# Arena2_0.net
KiCad netlist of a schematic drawn in Altium Designer
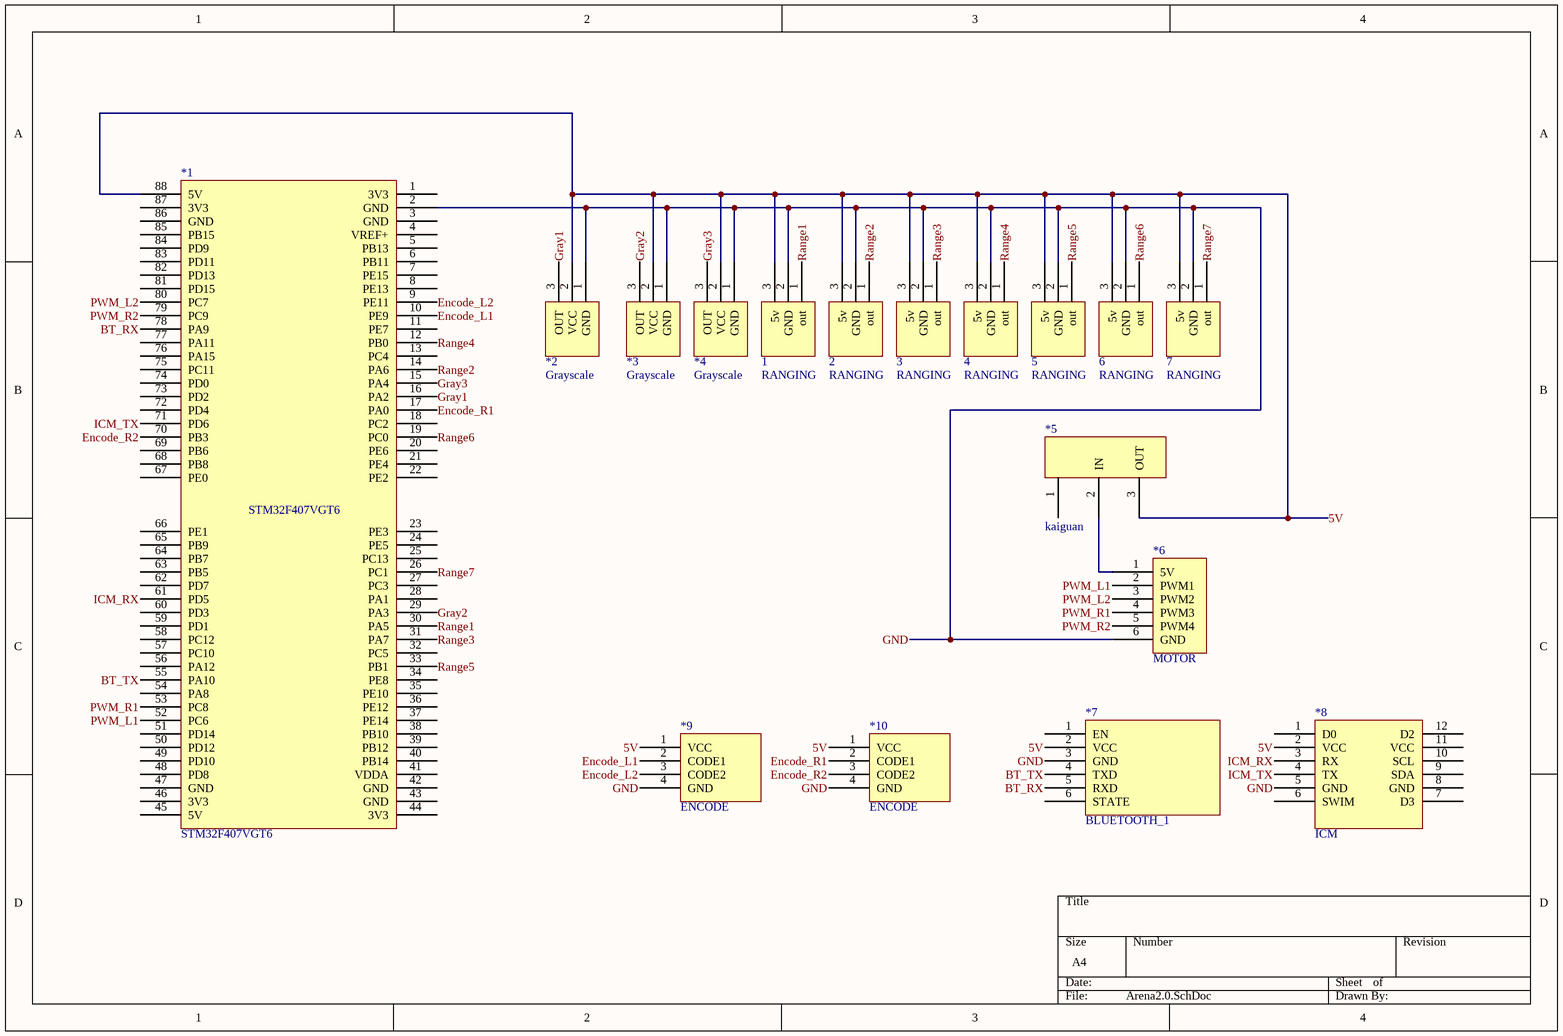
[diagram p0: Arena2.0.SchDoc]

(export (version "E")
  (design (tool "Eeschema 10.0.6"))
  (components
    (comp (ref "*1")
      (value "STM32F407VGT6")
      (footprint "STM32F407VGT6")
      (libsource (lib "Arena") (part "STM32F407VGT6"))
    )
    (comp (ref "*2")
      (value "Grayscale")
      (footprint "PH2.0-L-Z-3P")
      (libsource (lib "Arena") (part "Grayscale"))
    )
    (comp (ref "*3")
      (value "Grayscale")
      (footprint "PH2.0-L-Z-3P")
      (libsource (lib "Arena") (part "Grayscale"))
    )
    (comp (ref "*4")
      (value "Grayscale")
      (footprint "PH2.0-L-Z-3P")
      (libsource (lib "Arena") (part "Grayscale"))
    )
    (comp (ref "*5") (value "kaiguan") (footprint "kaiguan") (libsource (lib "Arena") (part "kaiguan")))
    (comp (ref "*6") (value "MOTOR") (footprint "PH2.0-L-Z-6P") (libsource (lib "Arena") (part "MOTOR")))
    (comp (ref "*7")
      (value "BLUETOOTH_1")
      (footprint "bluetooth")
      (libsource (lib "Arena") (part "BLUETOOTH_1"))
    )
    (comp (ref "*8") (value "ICM") (footprint "ICM") (libsource (lib "Arena") (part "ICM")))
    (comp (ref "*9") (value "ENCODE") (footprint "PH2.0-L-Z-4P") (libsource (lib "Arena") (part "ENCODE")))
    (comp (ref "*10") (value "ENCODE") (footprint "PH2.0-L-Z-4P") (libsource (lib "Arena") (part "ENCODE")))
    (comp (ref "1") (value "RANGING") (footprint "PH2.0-L-Z-3P") (libsource (lib "Arena") (part "RANGING")))
    (comp (ref "2") (value "RANGING") (footprint "PH2.0-L-Z-3P") (libsource (lib "Arena") (part "RANGING")))
    (comp (ref "3") (value "RANGING") (footprint "PH2.0-L-Z-3P") (libsource (lib "Arena") (part "RANGING")))
    (comp (ref "4") (value "RANGING") (footprint "PH2.0-L-Z-3P") (libsource (lib "Arena") (part "RANGING")))
    (comp (ref "5") (value "RANGING") (footprint "PH2.0-L-Z-3P") (libsource (lib "Arena") (part "RANGING")))
    (comp (ref "6") (value "RANGING") (footprint "PH2.0-L-Z-3P") (libsource (lib "Arena") (part "RANGING")))
    (comp (ref "7") (value "RANGING") (footprint "PH2.0-L-Z-3P") (libsource (lib "Arena") (part "RANGING")))
  )
  (nets
    (net (code "1") (name "/5V") (class "Default")
      (node (ref "*1") (pin "88") (pinfunction "5V_88") (pintype "passive"))
      (node (ref "*10") (pin "1") (pinfunction "VCC_1") (pintype "passive"))
      (node (ref "*2") (pin "2") (pinfunction "VCC_2") (pintype "passive"))
      (node (ref "*3") (pin "2") (pinfunction "VCC_2") (pintype "passive"))
      (node (ref "*4") (pin "2") (pinfunction "VCC_2") (pintype "passive"))
      (node (ref "*5") (pin "3") (pinfunction "OUT_3") (pintype "passive"))
      (node (ref "*7") (pin "2") (pinfunction "VCC_2") (pintype "passive"))
      (node (ref "*8") (pin "2") (pinfunction "VCC_2") (pintype "passive"))
      (node (ref "*9") (pin "1") (pinfunction "VCC_1") (pintype "passive"))
      (node (ref "1") (pin "3") (pinfunction "5v_3") (pintype "passive"))
      (node (ref "2") (pin "3") (pinfunction "5v_3") (pintype "passive"))
      (node (ref "3") (pin "3") (pinfunction "5v_3") (pintype "passive"))
      (node (ref "4") (pin "3") (pinfunction "5v_3") (pintype "passive"))
      (node (ref "5") (pin "3") (pinfunction "5v_3") (pintype "passive"))
      (node (ref "6") (pin "3") (pinfunction "5v_3") (pintype "passive"))
      (node (ref "7") (pin "3") (pinfunction "5v_3") (pintype "passive"))
    )
    (net (code "2") (name "/BT_RX") (class "Default")
      (node (ref "*1") (pin "78") (pinfunction "PA9_78") (pintype "passive"))
      (node (ref "*7") (pin "5") (pinfunction "RXD_5") (pintype "passive"))
    )
    (net (code "3") (name "/BT_TX") (class "Default")
      (node (ref "*1") (pin "55") (pinfunction "PA10_55") (pintype "passive"))
      (node (ref "*7") (pin "4") (pinfunction "TXD_4") (pintype "passive"))
    )
    (net (code "4") (name "/Encode_L1") (class "Default")
      (node (ref "*1") (pin "10") (pinfunction "PE9_10") (pintype "passive"))
      (node (ref "*9") (pin "2") (pinfunction "CODE1_2") (pintype "passive"))
    )
    (net (code "5") (name "/Encode_L2") (class "Default")
      (node (ref "*1") (pin "9") (pinfunction "PE11_9") (pintype "passive"))
      (node (ref "*9") (pin "3") (pinfunction "CODE2_3") (pintype "passive"))
    )
    (net (code "6") (name "/Encode_R1") (class "Default")
      (node (ref "*1") (pin "17") (pinfunction "PA0_17") (pintype "passive"))
      (node (ref "*10") (pin "2") (pinfunction "CODE1_2") (pintype "passive"))
    )
    (net (code "7") (name "/Encode_R2") (class "Default")
      (node (ref "*1") (pin "70") (pinfunction "PB3_70") (pintype "passive"))
      (node (ref "*10") (pin "3") (pinfunction "CODE2_3") (pintype "passive"))
    )
    (net (code "8") (name "/GND") (class "Default")
      (node (ref "*1") (pin "2") (pinfunction "GND_2") (pintype "passive"))
      (node (ref "*10") (pin "4") (pinfunction "GND_4") (pintype "passive"))
      (node (ref "*2") (pin "1") (pinfunction "GND_1") (pintype "passive"))
      (node (ref "*3") (pin "1") (pinfunction "GND_1") (pintype "passive"))
      (node (ref "*4") (pin "1") (pinfunction "GND_1") (pintype "passive"))
      (node (ref "*6") (pin "6") (pinfunction "GND_6") (pintype "passive"))
      (node (ref "*7") (pin "3") (pinfunction "GND_3") (pintype "passive"))
      (node (ref "*8") (pin "5") (pinfunction "GND_5") (pintype "passive"))
      (node (ref "*9") (pin "4") (pinfunction "GND_4") (pintype "passive"))
      (node (ref "1") (pin "2") (pinfunction "GND_2") (pintype "passive"))
      (node (ref "2") (pin "2") (pinfunction "GND_2") (pintype "passive"))
      (node (ref "3") (pin "2") (pinfunction "GND_2") (pintype "passive"))
      (node (ref "4") (pin "2") (pinfunction "GND_2") (pintype "passive"))
      (node (ref "5") (pin "2") (pinfunction "GND_2") (pintype "passive"))
      (node (ref "6") (pin "2") (pinfunction "GND_2") (pintype "passive"))
      (node (ref "7") (pin "2") (pinfunction "GND_2") (pintype "passive"))
    )
    (net (code "9") (name "/Gray1") (class "Default")
      (node (ref "*1") (pin "16") (pinfunction "PA2_16") (pintype "passive"))
      (node (ref "*2") (pin "3") (pinfunction "OUT_3") (pintype "passive"))
    )
    (net (code "10") (name "/Gray2") (class "Default")
      (node (ref "*1") (pin "29") (pinfunction "PA3_29") (pintype "passive"))
      (node (ref "*3") (pin "3") (pinfunction "OUT_3") (pintype "passive"))
    )
    (net (code "11") (name "/Gray3") (class "Default")
      (node (ref "*1") (pin "15") (pinfunction "PA4_15") (pintype "passive"))
      (node (ref "*4") (pin "3") (pinfunction "OUT_3") (pintype "passive"))
    )
    (net (code "12") (name "/ICM_RX") (class "Default")
      (node (ref "*1") (pin "61") (pinfunction "PD5_61") (pintype "passive"))
      (node (ref "*8") (pin "3") (pinfunction "RX_3") (pintype "passive"))
    )
    (net (code "13") (name "/ICM_TX") (class "Default")
      (node (ref "*1") (pin "71") (pinfunction "PD6_71") (pintype "passive"))
      (node (ref "*8") (pin "4") (pinfunction "TX_4") (pintype "passive"))
    )
    (net (code "14") (name "/PWM_L1") (class "Default")
      (node (ref "*1") (pin "52") (pinfunction "PC6_52") (pintype "passive"))
      (node (ref "*6") (pin "2") (pinfunction "PWM1_2") (pintype "passive"))
    )
    (net (code "15") (name "/PWM_L2") (class "Default")
      (node (ref "*1") (pin "80") (pinfunction "PC7_80") (pintype "passive"))
      (node (ref "*6") (pin "3") (pinfunction "PWM2_3") (pintype "passive"))
    )
    (net (code "16") (name "/PWM_R1") (class "Default")
      (node (ref "*1") (pin "53") (pinfunction "PC8_53") (pintype "passive"))
      (node (ref "*6") (pin "4") (pinfunction "PWM3_4") (pintype "passive"))
    )
    (net (code "17") (name "/PWM_R2") (class "Default")
      (node (ref "*1") (pin "79") (pinfunction "PC9_79") (pintype "passive"))
      (node (ref "*6") (pin "5") (pinfunction "PWM4_5") (pintype "passive"))
    )
    (net (code "18") (name "/Range1") (class "Default")
      (node (ref "*1") (pin "30") (pinfunction "PA5_30") (pintype "passive"))
      (node (ref "1") (pin "1") (pinfunction "out_1") (pintype "passive"))
    )
    (net (code "19") (name "/Range2") (class "Default")
      (node (ref "*1") (pin "14") (pinfunction "PA6_14") (pintype "passive"))
      (node (ref "2") (pin "1") (pinfunction "out_1") (pintype "passive"))
    )
    (net (code "20") (name "/Range3") (class "Default")
      (node (ref "*1") (pin "31") (pinfunction "PA7_31") (pintype "passive"))
      (node (ref "3") (pin "1") (pinfunction "out_1") (pintype "passive"))
    )
    (net (code "21") (name "/Range4") (class "Default")
      (node (ref "*1") (pin "12") (pinfunction "PB0_12") (pintype "passive"))
      (node (ref "4") (pin "1") (pinfunction "out_1") (pintype "passive"))
    )
    (net (code "22") (name "/Range5") (class "Default")
      (node (ref "*1") (pin "33") (pinfunction "PB1_33") (pintype "passive"))
      (node (ref "5") (pin "1") (pinfunction "out_1") (pintype "passive"))
    )
    (net (code "23") (name "/Range6") (class "Default")
      (node (ref "*1") (pin "19") (pinfunction "PC0_19") (pintype "passive"))
      (node (ref "6") (pin "1") (pinfunction "out_1") (pintype "passive"))
    )
    (net (code "24") (name "/Range7") (class "Default")
      (node (ref "*1") (pin "26") (pinfunction "PC1_26") (pintype "passive"))
      (node (ref "7") (pin "1") (pinfunction "out_1") (pintype "passive"))
    )
    (net (code "25") (name "Net-(*5-IN)") (class "Default")
      (node (ref "*5") (pin "2") (pinfunction "IN_2") (pintype "passive"))
      (node (ref "*6") (pin "1") (pinfunction "5V_1") (pintype "passive"))
    )
    (net (code "26") (name "unconnected-(*1-3V3-Pad1)") (class "Default")
      (node (ref "*1") (pin "1") (pinfunction "3V3_1") (pintype "passive"))
    )
    (net (code "27") (name "unconnected-(*1-3V3-Pad44)") (class "Default")
      (node (ref "*1") (pin "44") (pinfunction "3V3_44") (pintype "passive"))
    )
    (net (code "28") (name "unconnected-(*1-3V3-Pad46)") (class "Default")
      (node (ref "*1") (pin "46") (pinfunction "3V3_46") (pintype "passive"))
    )
    (net (code "29") (name "unconnected-(*1-3V3-Pad87)") (class "Default")
      (node (ref "*1") (pin "87") (pinfunction "3V3_87") (pintype "passive"))
    )
    (net (code "30") (name "unconnected-(*1-5V-Pad45)") (class "Default")
      (node (ref "*1") (pin "45") (pinfunction "5V_45") (pintype "passive"))
    )
    (net (code "31") (name "unconnected-(*1-GND-Pad3)") (class "Default")
      (node (ref "*1") (pin "3") (pinfunction "GND_3") (pintype "passive"))
    )
    (net (code "32") (name "unconnected-(*1-GND-Pad42)") (class "Default")
      (node (ref "*1") (pin "42") (pinfunction "GND_42") (pintype "passive"))
    )
    (net (code "33") (name "unconnected-(*1-GND-Pad43)") (class "Default")
      (node (ref "*1") (pin "43") (pinfunction "GND_43") (pintype "passive"))
    )
    (net (code "34") (name "unconnected-(*1-GND-Pad47)") (class "Default")
      (node (ref "*1") (pin "47") (pinfunction "GND_47") (pintype "passive"))
    )
    (net (code "35") (name "unconnected-(*1-GND-Pad86)") (class "Default")
      (node (ref "*1") (pin "86") (pinfunction "GND_86") (pintype "passive"))
    )
    (net (code "36") (name "unconnected-(*1-PA1-Pad28)") (class "Default")
      (node (ref "*1") (pin "28") (pinfunction "PA1_28") (pintype "passive"))
    )
    (net (code "37") (name "unconnected-(*1-PA8-Pad54)") (class "Default")
      (node (ref "*1") (pin "54") (pinfunction "PA8_54") (pintype "passive"))
    )
    (net (code "38") (name "unconnected-(*1-PA11-Pad77)") (class "Default")
      (node (ref "*1") (pin "77") (pinfunction "PA11_77") (pintype "passive"))
    )
    (net (code "39") (name "unconnected-(*1-PA12-Pad56)") (class "Default")
      (node (ref "*1") (pin "56") (pinfunction "PA12_56") (pintype "passive"))
    )
    (net (code "40") (name "unconnected-(*1-PA15-Pad76)") (class "Default")
      (node (ref "*1") (pin "76") (pinfunction "PA15_76") (pintype "passive"))
    )
    (net (code "41") (name "unconnected-(*1-PB5-Pad63)") (class "Default")
      (node (ref "*1") (pin "63") (pinfunction "PB5_63") (pintype "passive"))
    )
    (net (code "42") (name "unconnected-(*1-PB6-Pad69)") (class "Default")
      (node (ref "*1") (pin "69") (pinfunction "PB6_69") (pintype "passive"))
    )
    (net (code "43") (name "unconnected-(*1-PB7-Pad64)") (class "Default")
      (node (ref "*1") (pin "64") (pinfunction "PB7_64") (pintype "passive"))
    )
    (net (code "44") (name "unconnected-(*1-PB8-Pad68)") (class "Default")
      (node (ref "*1") (pin "68") (pinfunction "PB8_68") (pintype "passive"))
    )
    (net (code "45") (name "unconnected-(*1-PB9-Pad65)") (class "Default")
      (node (ref "*1") (pin "65") (pinfunction "PB9_65") (pintype "passive"))
    )
    (net (code "46") (name "unconnected-(*1-PB10-Pad38)") (class "Default")
      (node (ref "*1") (pin "38") (pinfunction "PB10_38") (pintype "passive"))
    )
    (net (code "47") (name "unconnected-(*1-PB11-Pad6)") (class "Default")
      (node (ref "*1") (pin "6") (pinfunction "PB11_6") (pintype "passive"))
    )
    (net (code "48") (name "unconnected-(*1-PB12-Pad39)") (class "Default")
      (node (ref "*1") (pin "39") (pinfunction "PB12_39") (pintype "passive"))
    )
    (net (code "49") (name "unconnected-(*1-PB13-Pad5)") (class "Default")
      (node (ref "*1") (pin "5") (pinfunction "PB13_5") (pintype "passive"))
    )
    (net (code "50") (name "unconnected-(*1-PB14-Pad40)") (class "Default")
      (node (ref "*1") (pin "40") (pinfunction "PB14_40") (pintype "passive"))
    )
    (net (code "51") (name "unconnected-(*1-PB15-Pad85)") (class "Default")
      (node (ref "*1") (pin "85") (pinfunction "PB15_85") (pintype "passive"))
    )
    (net (code "52") (name "unconnected-(*1-PC2-Pad18)") (class "Default")
      (node (ref "*1") (pin "18") (pinfunction "PC2_18") (pintype "passive"))
    )
    (net (code "53") (name "unconnected-(*1-PC3-Pad27)") (class "Default")
      (node (ref "*1") (pin "27") (pinfunction "PC3_27") (pintype "passive"))
    )
    (net (code "54") (name "unconnected-(*1-PC4-Pad13)") (class "Default")
      (node (ref "*1") (pin "13") (pinfunction "PC4_13") (pintype "passive"))
    )
    (net (code "55") (name "unconnected-(*1-PC5-Pad32)") (class "Default")
      (node (ref "*1") (pin "32") (pinfunction "PC5_32") (pintype "passive"))
    )
    (net (code "56") (name "unconnected-(*1-PC10-Pad57)") (class "Default")
      (node (ref "*1") (pin "57") (pinfunction "PC10_57") (pintype "passive"))
    )
    (net (code "57") (name "unconnected-(*1-PC11-Pad75)") (class "Default")
      (node (ref "*1") (pin "75") (pinfunction "PC11_75") (pintype "passive"))
    )
    (net (code "58") (name "unconnected-(*1-PC12-Pad58)") (class "Default")
      (node (ref "*1") (pin "58") (pinfunction "PC12_58") (pintype "passive"))
    )
    (net (code "59") (name "unconnected-(*1-PC13-Pad25)") (class "Default")
      (node (ref "*1") (pin "25") (pinfunction "PC13_25") (pintype "passive"))
    )
    (net (code "60") (name "unconnected-(*1-PD0-Pad74)") (class "Default")
      (node (ref "*1") (pin "74") (pinfunction "PD0_74") (pintype "passive"))
    )
    (net (code "61") (name "unconnected-(*1-PD1-Pad59)") (class "Default")
      (node (ref "*1") (pin "59") (pinfunction "PD1_59") (pintype "passive"))
    )
    (net (code "62") (name "unconnected-(*1-PD2-Pad73)") (class "Default")
      (node (ref "*1") (pin "73") (pinfunction "PD2_73") (pintype "passive"))
    )
    (net (code "63") (name "unconnected-(*1-PD3-Pad60)") (class "Default")
      (node (ref "*1") (pin "60") (pinfunction "PD3_60") (pintype "passive"))
    )
    (net (code "64") (name "unconnected-(*1-PD4-Pad72)") (class "Default")
      (node (ref "*1") (pin "72") (pinfunction "PD4_72") (pintype "passive"))
    )
    (net (code "65") (name "unconnected-(*1-PD7-Pad62)") (class "Default")
      (node (ref "*1") (pin "62") (pinfunction "PD7_62") (pintype "passive"))
    )
    (net (code "66") (name "unconnected-(*1-PD8-Pad48)") (class "Default")
      (node (ref "*1") (pin "48") (pinfunction "PD8_48") (pintype "passive"))
    )
    (net (code "67") (name "unconnected-(*1-PD9-Pad84)") (class "Default")
      (node (ref "*1") (pin "84") (pinfunction "PD9_84") (pintype "passive"))
    )
    (net (code "68") (name "unconnected-(*1-PD10-Pad49)") (class "Default")
      (node (ref "*1") (pin "49") (pinfunction "PD10_49") (pintype "passive"))
    )
    (net (code "69") (name "unconnected-(*1-PD11-Pad83)") (class "Default")
      (node (ref "*1") (pin "83") (pinfunction "PD11_83") (pintype "passive"))
    )
    (net (code "70") (name "unconnected-(*1-PD12-Pad50)") (class "Default")
      (node (ref "*1") (pin "50") (pinfunction "PD12_50") (pintype "passive"))
    )
    (net (code "71") (name "unconnected-(*1-PD13-Pad82)") (class "Default")
      (node (ref "*1") (pin "82") (pinfunction "PD13_82") (pintype "passive"))
    )
    (net (code "72") (name "unconnected-(*1-PD14-Pad51)") (class "Default")
      (node (ref "*1") (pin "51") (pinfunction "PD14_51") (pintype "passive"))
    )
    (net (code "73") (name "unconnected-(*1-PD15-Pad81)") (class "Default")
      (node (ref "*1") (pin "81") (pinfunction "PD15_81") (pintype "passive"))
    )
    (net (code "74") (name "unconnected-(*1-PE0-Pad67)") (class "Default")
      (node (ref "*1") (pin "67") (pinfunction "PE0_67") (pintype "passive"))
    )
    (net (code "75") (name "unconnected-(*1-PE1-Pad66)") (class "Default")
      (node (ref "*1") (pin "66") (pinfunction "PE1_66") (pintype "passive"))
    )
    (net (code "76") (name "unconnected-(*1-PE2-Pad22)") (class "Default")
      (node (ref "*1") (pin "22") (pinfunction "PE2_22") (pintype "passive"))
    )
    (net (code "77") (name "unconnected-(*1-PE3-Pad23)") (class "Default")
      (node (ref "*1") (pin "23") (pinfunction "PE3_23") (pintype "passive"))
    )
    (net (code "78") (name "unconnected-(*1-PE4-Pad21)") (class "Default")
      (node (ref "*1") (pin "21") (pinfunction "PE4_21") (pintype "passive"))
    )
    (net (code "79") (name "unconnected-(*1-PE5-Pad24)") (class "Default")
      (node (ref "*1") (pin "24") (pinfunction "PE5_24") (pintype "passive"))
    )
    (net (code "80") (name "unconnected-(*1-PE6-Pad20)") (class "Default")
      (node (ref "*1") (pin "20") (pinfunction "PE6_20") (pintype "passive"))
    )
    (net (code "81") (name "unconnected-(*1-PE7-Pad11)") (class "Default")
      (node (ref "*1") (pin "11") (pinfunction "PE7_11") (pintype "passive"))
    )
    (net (code "82") (name "unconnected-(*1-PE8-Pad34)") (class "Default")
      (node (ref "*1") (pin "34") (pinfunction "PE8_34") (pintype "passive"))
    )
    (net (code "83") (name "unconnected-(*1-PE10-Pad35)") (class "Default")
      (node (ref "*1") (pin "35") (pinfunction "PE10_35") (pintype "passive"))
    )
    (net (code "84") (name "unconnected-(*1-PE12-Pad36)") (class "Default")
      (node (ref "*1") (pin "36") (pinfunction "PE12_36") (pintype "passive"))
    )
    (net (code "85") (name "unconnected-(*1-PE13-Pad8)") (class "Default")
      (node (ref "*1") (pin "8") (pinfunction "PE13_8") (pintype "passive"))
    )
    (net (code "86") (name "unconnected-(*1-PE14-Pad37)") (class "Default")
      (node (ref "*1") (pin "37") (pinfunction "PE14_37") (pintype "passive"))
    )
    (net (code "87") (name "unconnected-(*1-PE15-Pad7)") (class "Default")
      (node (ref "*1") (pin "7") (pinfunction "PE15_7") (pintype "passive"))
    )
    (net (code "88") (name "unconnected-(*1-VDDA-Pad41)") (class "Default")
      (node (ref "*1") (pin "41") (pinfunction "VDDA_41") (pintype "passive"))
    )
    (net (code "89") (name "unconnected-(*1-VREF+-Pad4)") (class "Default")
      (node (ref "*1") (pin "4") (pinfunction "VREF+_4") (pintype "passive"))
    )
    (net (code "90") (name "unconnected-(*5-Pad1)") (class "Default")
      (node (ref "*5") (pin "1") (pintype "passive"))
    )
    (net (code "91") (name "unconnected-(*7-EN-Pad1)") (class "Default")
      (node (ref "*7") (pin "1") (pinfunction "EN_1") (pintype "passive"))
    )
    (net (code "92") (name "unconnected-(*7-STATE-Pad6)") (class "Default")
      (node (ref "*7") (pin "6") (pinfunction "STATE_6") (pintype "passive"))
    )
    (net (code "93") (name "unconnected-(*8-D0-Pad1)") (class "Default")
      (node (ref "*8") (pin "1") (pinfunction "D0_1") (pintype "passive"))
    )
    (net (code "94") (name "unconnected-(*8-D2-Pad12)") (class "Default")
      (node (ref "*8") (pin "12") (pinfunction "D2_12") (pintype "passive"))
    )
    (net (code "95") (name "unconnected-(*8-D3-Pad7)") (class "Default")
      (node (ref "*8") (pin "7") (pinfunction "D3_7") (pintype "passive"))
    )
    (net (code "96") (name "unconnected-(*8-GND-Pad8)") (class "Default")
      (node (ref "*8") (pin "8") (pinfunction "GND_8") (pintype "passive"))
    )
    (net (code "97") (name "unconnected-(*8-SCL-Pad10)") (class "Default")
      (node (ref "*8") (pin "10") (pinfunction "SCL_10") (pintype "passive"))
    )
    (net (code "98") (name "unconnected-(*8-SDA-Pad9)") (class "Default")
      (node (ref "*8") (pin "9") (pinfunction "SDA_9") (pintype "passive"))
    )
    (net (code "99") (name "unconnected-(*8-SWIM-Pad6)") (class "Default")
      (node (ref "*8") (pin "6") (pinfunction "SWIM_6") (pintype "passive"))
    )
    (net (code "100") (name "unconnected-(*8-VCC-Pad11)") (class "Default")
      (node (ref "*8") (pin "11") (pinfunction "VCC_11") (pintype "passive"))
    )
  )
)
